# FFB_Arduino_Yoke_1_2_Micro.net
KiCad netlist of a schematic drawn in EasyEDA
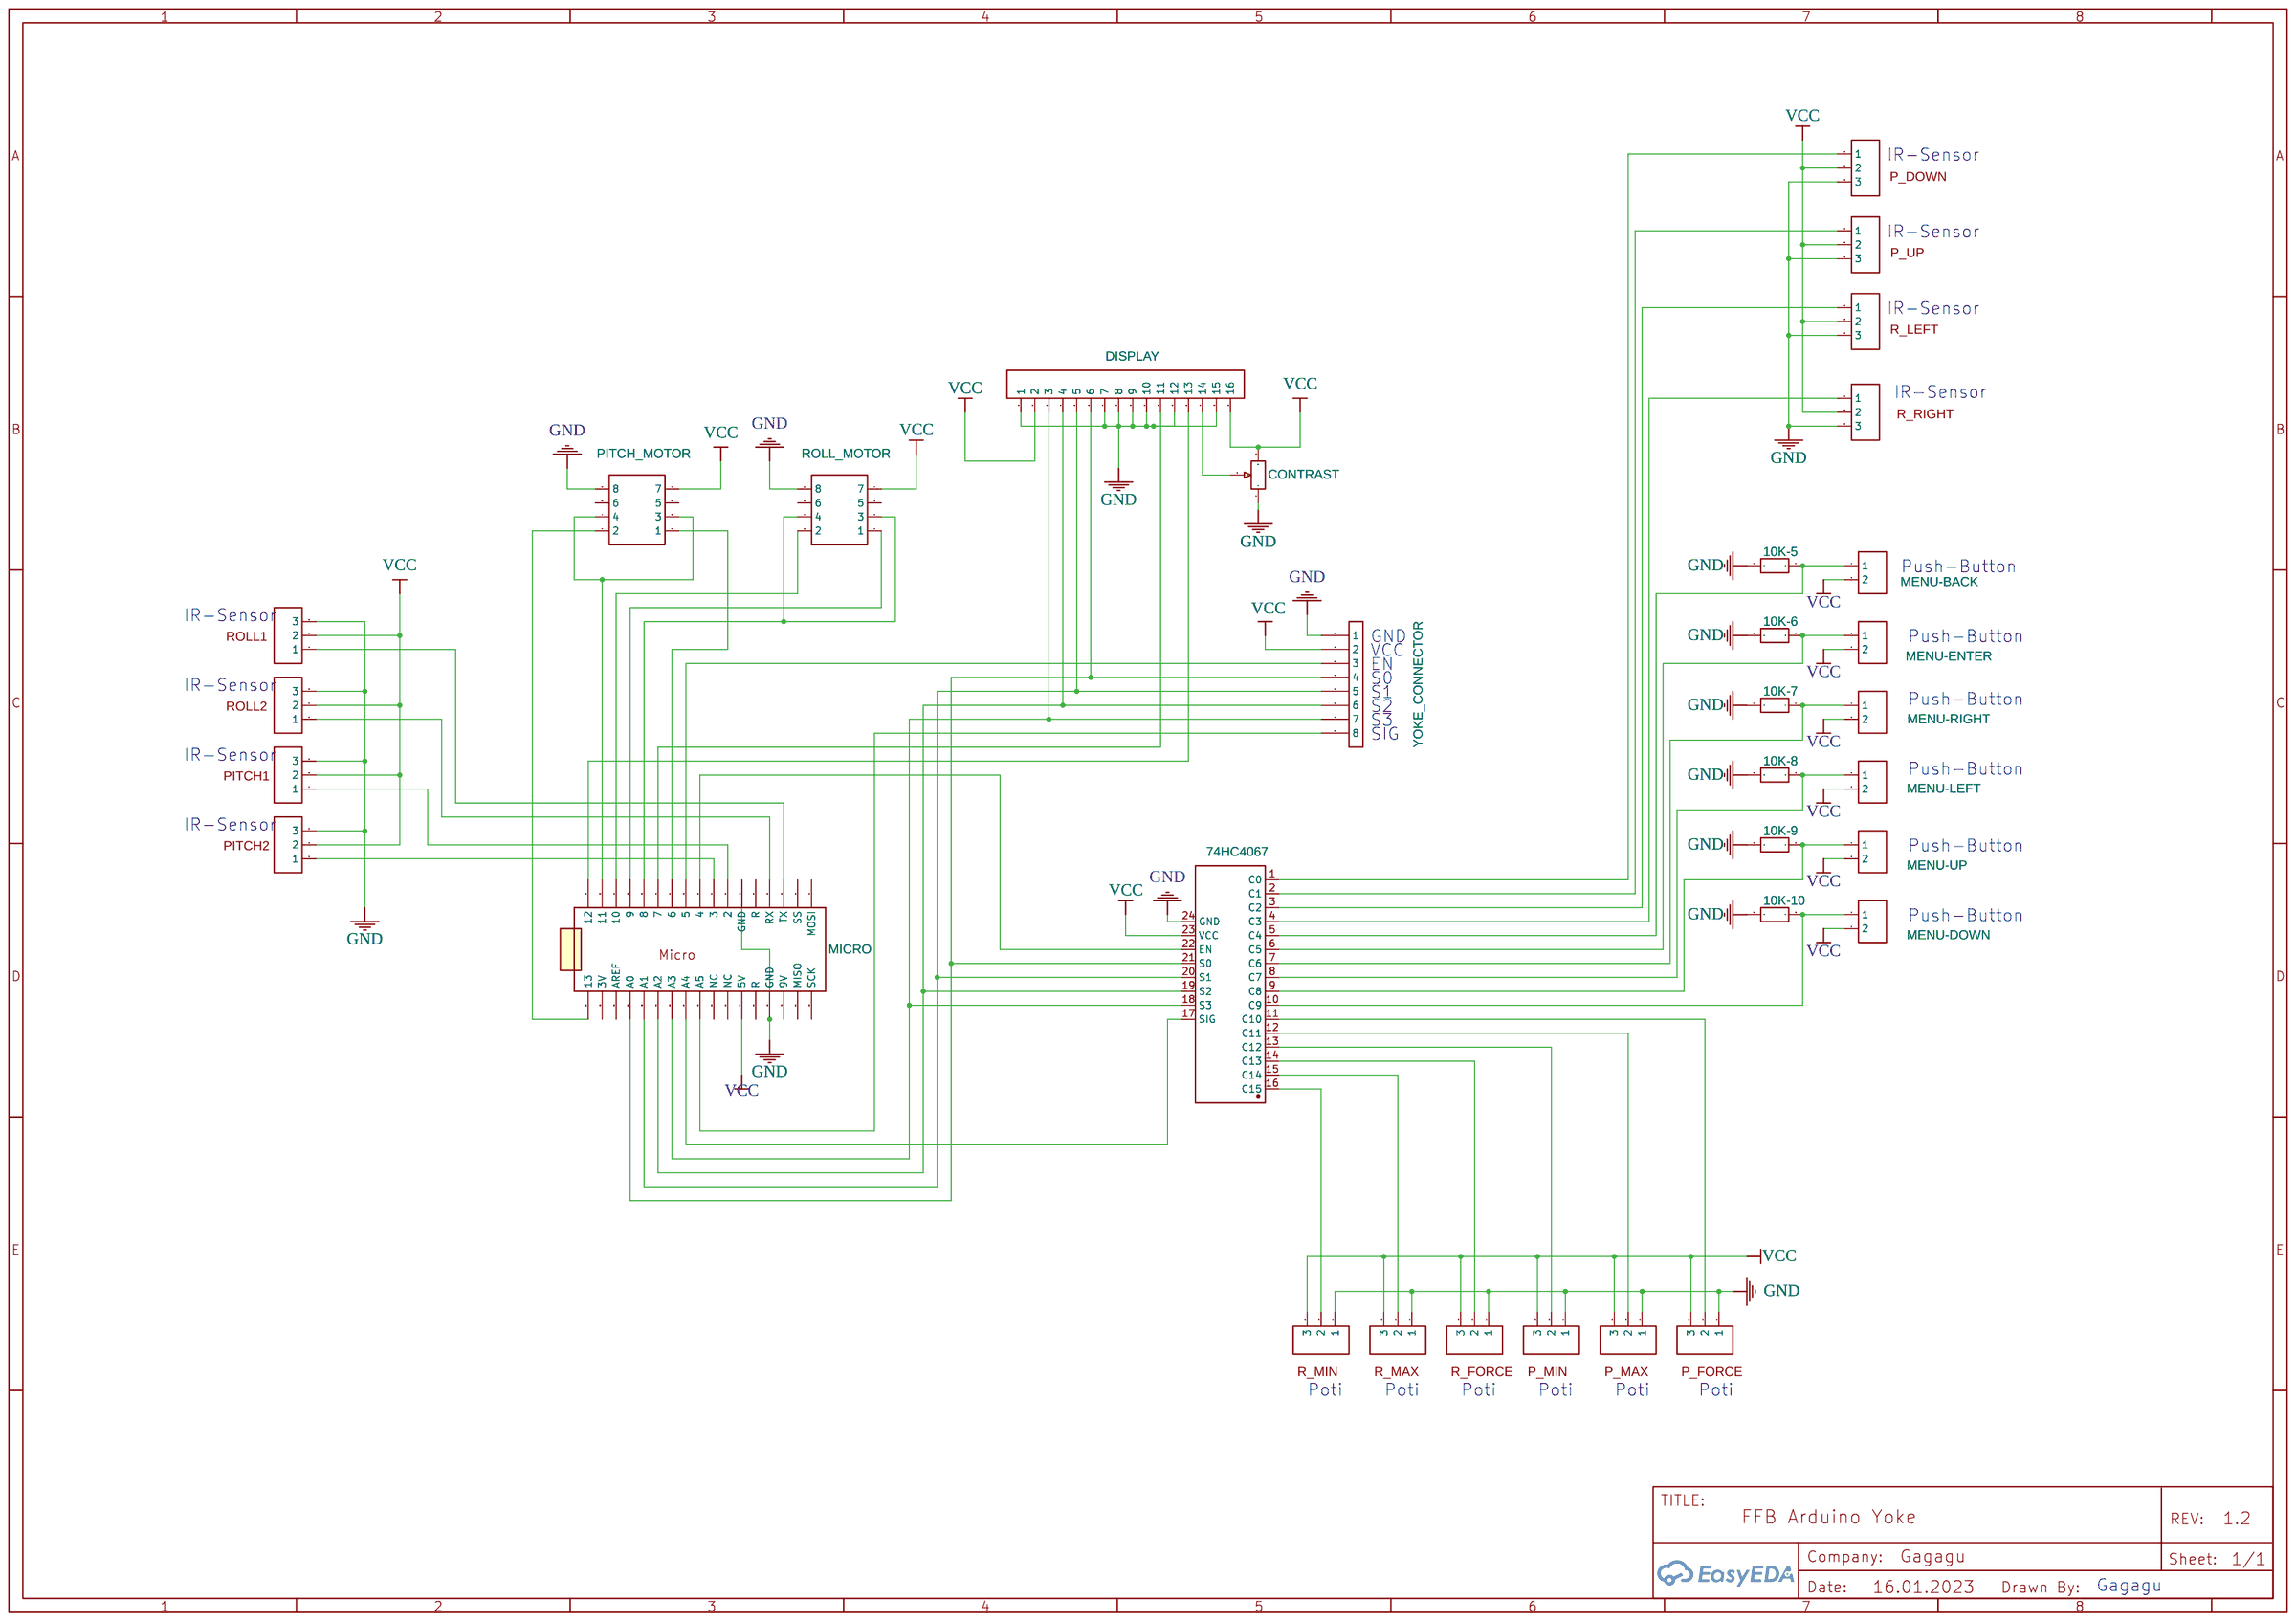
[diagram p0: schematic sheet]

(export (version "E")
  (design (tool "Eeschema 10.0.6"))
  (components
    (comp (ref "10K-5") (value "10k") (libsource (lib "") (part "R_AXIAL-0.3_EU")))
    (comp (ref "10K-6") (value "10k") (libsource (lib "") (part "R_AXIAL-0.3_EU")))
    (comp (ref "10K-7") (value "10k") (libsource (lib "") (part "R_AXIAL-0.3_EU")))
    (comp (ref "10K-8") (value "10k") (libsource (lib "") (part "R_AXIAL-0.3_EU")))
    (comp (ref "10K-9") (value "10k") (libsource (lib "") (part "R_AXIAL-0.3_EU")))
    (comp (ref "10K-10") (value "10k") (libsource (lib "") (part "R_AXIAL-0.3_EU")))
    (comp (ref "74HC4067")
      (value "MUX CD74HC4067")
      (fields (field (name "BOM_Supplier Part") "420243"))
      (libsource (lib "") (part "16-Kanal Analog/Digital Multiplexer MUX CD74HC4067"))
    )
    (comp (ref "CONTRAST") (value "R_3386P_EU") (libsource (lib "") (part "R_3386P_EU")))
    (comp (ref "DISPLAY") (value "HDR-M-2.54_1x16") (libsource (lib "") (part "HDR-M-2.54_1x16")))
    (comp (ref "MENU-BACK")
      (value "HDR-F-2.54_1x2")
      (fields (field (name "BOM_Supplier Part") "C49661"))
      (libsource (lib "") (part "HDR-F-2.54_1x2_1"))
    )
    (comp (ref "MENU-DOWN")
      (value "HDR-F-2.54_1x2")
      (fields (field (name "BOM_Supplier Part") "C49661"))
      (libsource (lib "") (part "HDR-F-2.54_1x2_4"))
    )
    (comp (ref "MENU-ENTER")
      (value "HDR-F-2.54_1x2")
      (fields (field (name "BOM_Supplier Part") "C49661"))
      (libsource (lib "") (part "HDR-F-2.54_1x2"))
    )
    (comp (ref "MENU-LEFT")
      (value "HDR-F-2.54_1x2")
      (fields (field (name "BOM_Supplier Part") "C49661"))
      (libsource (lib "") (part "HDR-F-2.54_1x2_3"))
    )
    (comp (ref "MENU-RIGHT")
      (value "HDR-F-2.54_1x2")
      (fields (field (name "BOM_Supplier Part") "C49661"))
      (libsource (lib "") (part "HDR-F-2.54_1x2_5"))
    )
    (comp (ref "MENU-UP")
      (value "HDR-F-2.54_1x2")
      (fields (field (name "BOM_Supplier Part") "C49661"))
      (libsource (lib "") (part "HDR-F-2.54_1x2_2"))
    )
    (comp (ref "MICRO") (value "ARDUINOMICRO") (libsource (lib "") (part "ARDUINOMICRO")))
    (comp (ref "PITCH1")
      (value "Multiturn POT 10K")
      (fields (field (name "BOM_Supplier Part") "C146690"))
      (libsource (lib "") (part "HDR-F-2.54_1x3_5"))
    )
    (comp (ref "PITCH2")
      (value "Multiturn POT 10K")
      (fields (field (name "BOM_Supplier Part") "C146690"))
      (libsource (lib "") (part "HDR-F-2.54_1x3_1"))
    )
    (comp (ref "PITCH_MOTOR")
      (value "HDR-F-2.54_2x4")
      (fields (field (name "BOM_Supplier Part") "C239344"))
      (libsource (lib "") (part "HDR-F-2.54_2x4"))
    )
    (comp (ref "P_DOWN")
      (value "Multiturn POT 10K")
      (fields (field (name "BOM_Supplier Part") "C146690"))
      (libsource (lib "") (part "HDR-F-2.54_1x3_9"))
    )
    (comp (ref "P_FORCE")
      (value "Multiturn POT 10K")
      (fields (field (name "BOM_Supplier Part") "C146690"))
      (libsource (lib "") (part "HDR-F-2.54_1x3_11"))
    )
    (comp (ref "P_M;IN")
      (value "Multiturn POT 10K")
      (fields (field (name "BOM_Supplier Part") "C146690"))
      (libsource (lib "") (part "HDR-F-2.54_1x3_12"))
    )
    (comp (ref "P_MAX")
      (value "Multiturn POT 10K")
      (fields (field (name "BOM_Supplier Part") "C146690"))
      (libsource (lib "") (part "HDR-F-2.54_1x3_13"))
    )
    (comp (ref "P_UP")
      (value "Multiturn POT 10K")
      (fields (field (name "BOM_Supplier Part") "C146690"))
      (libsource (lib "") (part "HDR-F-2.54_1x3_7"))
    )
    (comp (ref "ROLL1")
      (value "Multiturn POT 10K")
      (fields (field (name "BOM_Supplier Part") "C146690"))
      (libsource (lib "") (part "HDR-F-2.54_1x3_10"))
    )
    (comp (ref "ROLL2")
      (value "Multiturn POT 10K")
      (fields (field (name "BOM_Supplier Part") "C146690"))
      (libsource (lib "") (part "HDR-F-2.54_1x3"))
    )
    (comp (ref "ROLL_MOTOR")
      (value "HDR-F-2.54_2x4")
      (fields (field (name "BOM_Supplier Part") "C239344"))
      (libsource (lib "") (part "HDR-F-2.54_2x4_1"))
    )
    (comp (ref "R_FORCE")
      (value "Multiturn POT 10K")
      (fields (field (name "BOM_Supplier Part") "C146690"))
      (libsource (lib "") (part "HDR-F-2.54_1x3_6"))
    )
    (comp (ref "R_LEFT")
      (value "Multiturn POT 10K")
      (fields (field (name "BOM_Supplier Part") "C146690"))
      (libsource (lib "") (part "HDR-F-2.54_1x3_2"))
    )
    (comp (ref "R_MAX")
      (value "Multiturn POT 10K")
      (fields (field (name "BOM_Supplier Part") "C146690"))
      (libsource (lib "") (part "HDR-F-2.54_1x3_8"))
    )
    (comp (ref "R_MIN")
      (value "Multiturn POT 10K")
      (fields (field (name "BOM_Supplier Part") "C146690"))
      (libsource (lib "") (part "HDR-F-2.54_1x3_3"))
    )
    (comp (ref "R_RIGHT")
      (value "Multiturn POT 10K")
      (fields (field (name "BOM_Supplier Part") "C146690"))
      (libsource (lib "") (part "HDR-F-2.54_1x3_4"))
    )
    (comp (ref "YOKE_CONNECTOR")
      (value "Yoke Connector")
      (fields (field (name "BOM_Manufacturer Part") "Conector_dupont"))
      (libsource (lib "") (part "DUPONT_1X8"))
    )
  )
  (nets
    (net (code "1") (name "GND") (class "Default")
      (node (ref "10K-10") (pin "1") (pinfunction "1_1") (pintype "unspecified"))
      (node (ref "10K-5") (pin "1") (pinfunction "1_1") (pintype "unspecified"))
      (node (ref "10K-6") (pin "1") (pinfunction "1_1") (pintype "unspecified"))
      (node (ref "10K-7") (pin "1") (pinfunction "1_1") (pintype "unspecified"))
      (node (ref "10K-8") (pin "1") (pinfunction "1_1") (pintype "unspecified"))
      (node (ref "10K-9") (pin "1") (pinfunction "1_1") (pintype "unspecified"))
      (node (ref "74HC4067") (pin "24") (pinfunction "GND_24") (pintype "unspecified"))
      (node (ref "CONTRAST") (pin "1") (pinfunction "1_1") (pintype "input"))
      (node (ref "DISPLAY") (pin "1") (pinfunction "1_1") (pintype "unspecified"))
      (node (ref "DISPLAY") (pin "10") (pinfunction "10_10") (pintype "unspecified"))
      (node (ref "DISPLAY") (pin "12") (pinfunction "12_12") (pintype "unspecified"))
      (node (ref "DISPLAY") (pin "15") (pinfunction "15_15") (pintype "unspecified"))
      (node (ref "DISPLAY") (pin "7") (pinfunction "7_7") (pintype "unspecified"))
      (node (ref "DISPLAY") (pin "8") (pinfunction "8_8") (pintype "unspecified"))
      (node (ref "DISPLAY") (pin "9") (pinfunction "9_9") (pintype "unspecified"))
      (node (ref "MICRO") (pin "P$12") (pinfunction "GND_P$12") (pintype "unspecified"))
      (node (ref "MICRO") (pin "P$21") (pinfunction "GND_P$21") (pintype "unspecified"))
      (node (ref "PITCH1") (pin "3") (pinfunction "3_3") (pintype "unspecified"))
      (node (ref "PITCH2") (pin "3") (pinfunction "3_3") (pintype "unspecified"))
      (node (ref "PITCH_MOTOR") (pin "8") (pinfunction "8_8") (pintype "unspecified"))
      (node (ref "P_DOWN") (pin "3") (pinfunction "3_3") (pintype "unspecified"))
      (node (ref "P_FORCE") (pin "1") (pinfunction "1_1") (pintype "unspecified"))
      (node (ref "P_M;IN") (pin "1") (pinfunction "1_1") (pintype "unspecified"))
      (node (ref "P_MAX") (pin "1") (pinfunction "1_1") (pintype "unspecified"))
      (node (ref "P_UP") (pin "3") (pinfunction "3_3") (pintype "unspecified"))
      (node (ref "ROLL1") (pin "3") (pinfunction "3_3") (pintype "unspecified"))
      (node (ref "ROLL2") (pin "3") (pinfunction "3_3") (pintype "unspecified"))
      (node (ref "ROLL_MOTOR") (pin "8") (pinfunction "8_8") (pintype "unspecified"))
      (node (ref "R_FORCE") (pin "1") (pinfunction "1_1") (pintype "unspecified"))
      (node (ref "R_LEFT") (pin "3") (pinfunction "3_3") (pintype "unspecified"))
      (node (ref "R_MAX") (pin "1") (pinfunction "1_1") (pintype "unspecified"))
      (node (ref "R_MIN") (pin "1") (pinfunction "1_1") (pintype "unspecified"))
      (node (ref "R_RIGHT") (pin "3") (pinfunction "3_3") (pintype "unspecified"))
      (node (ref "YOKE_CONNECTOR") (pin "1") (pinfunction "1_1") (pintype "unspecified"))
    )
    (net (code "2") (name "Net-(74HC4067-C0)") (class "Default")
      (node (ref "74HC4067") (pin "1") (pinfunction "C0_1") (pintype "unspecified"))
      (node (ref "P_DOWN") (pin "1") (pinfunction "1_1") (pintype "unspecified"))
    )
    (net (code "3") (name "Net-(74HC4067-C1)") (class "Default")
      (node (ref "74HC4067") (pin "2") (pinfunction "C1_2") (pintype "unspecified"))
      (node (ref "P_UP") (pin "1") (pinfunction "1_1") (pintype "unspecified"))
    )
    (net (code "4") (name "Net-(74HC4067-C2)") (class "Default")
      (node (ref "74HC4067") (pin "3") (pinfunction "C2_3") (pintype "unspecified"))
      (node (ref "R_LEFT") (pin "1") (pinfunction "1_1") (pintype "unspecified"))
    )
    (net (code "5") (name "Net-(74HC4067-C3)") (class "Default")
      (node (ref "74HC4067") (pin "4") (pinfunction "C3_4") (pintype "unspecified"))
      (node (ref "R_RIGHT") (pin "1") (pinfunction "1_1") (pintype "unspecified"))
    )
    (net (code "6") (name "Net-(74HC4067-C4)") (class "Default")
      (node (ref "10K-5") (pin "2") (pinfunction "2_2") (pintype "unspecified"))
      (node (ref "74HC4067") (pin "5") (pinfunction "C4_5") (pintype "unspecified"))
      (node (ref "MENU-BACK") (pin "1") (pinfunction "1_1") (pintype "input"))
    )
    (net (code "7") (name "Net-(74HC4067-C5)") (class "Default")
      (node (ref "10K-6") (pin "2") (pinfunction "2_2") (pintype "unspecified"))
      (node (ref "74HC4067") (pin "6") (pinfunction "C5_6") (pintype "unspecified"))
      (node (ref "MENU-ENTER") (pin "1") (pinfunction "1_1") (pintype "input"))
    )
    (net (code "8") (name "Net-(74HC4067-C6)") (class "Default")
      (node (ref "10K-7") (pin "2") (pinfunction "2_2") (pintype "unspecified"))
      (node (ref "74HC4067") (pin "7") (pinfunction "C6_7") (pintype "unspecified"))
      (node (ref "MENU-RIGHT") (pin "1") (pinfunction "1_1") (pintype "input"))
    )
    (net (code "9") (name "Net-(74HC4067-C7)") (class "Default")
      (node (ref "10K-8") (pin "2") (pinfunction "2_2") (pintype "unspecified"))
      (node (ref "74HC4067") (pin "8") (pinfunction "C7_8") (pintype "unspecified"))
      (node (ref "MENU-LEFT") (pin "1") (pinfunction "1_1") (pintype "input"))
    )
    (net (code "10") (name "Net-(74HC4067-C8)") (class "Default")
      (node (ref "10K-9") (pin "2") (pinfunction "2_2") (pintype "unspecified"))
      (node (ref "74HC4067") (pin "9") (pinfunction "C8_9") (pintype "unspecified"))
      (node (ref "MENU-UP") (pin "1") (pinfunction "1_1") (pintype "input"))
    )
    (net (code "11") (name "Net-(74HC4067-C9)") (class "Default")
      (node (ref "10K-10") (pin "2") (pinfunction "2_2") (pintype "unspecified"))
      (node (ref "74HC4067") (pin "10") (pinfunction "C9_10") (pintype "unspecified"))
      (node (ref "MENU-DOWN") (pin "1") (pinfunction "1_1") (pintype "input"))
    )
    (net (code "12") (name "Net-(74HC4067-C10)") (class "Default")
      (node (ref "74HC4067") (pin "11") (pinfunction "C10_11") (pintype "unspecified"))
      (node (ref "P_FORCE") (pin "2") (pinfunction "2_2") (pintype "unspecified"))
    )
    (net (code "13") (name "Net-(74HC4067-C11)") (class "Default")
      (node (ref "74HC4067") (pin "12") (pinfunction "C11_12") (pintype "unspecified"))
      (node (ref "P_MAX") (pin "2") (pinfunction "2_2") (pintype "unspecified"))
    )
    (net (code "14") (name "Net-(74HC4067-C12)") (class "Default")
      (node (ref "74HC4067") (pin "13") (pinfunction "C12_13") (pintype "unspecified"))
      (node (ref "P_M;IN") (pin "2") (pinfunction "2_2") (pintype "unspecified"))
    )
    (net (code "15") (name "Net-(74HC4067-C13)") (class "Default")
      (node (ref "74HC4067") (pin "14") (pinfunction "C13_14") (pintype "unspecified"))
      (node (ref "R_FORCE") (pin "2") (pinfunction "2_2") (pintype "unspecified"))
    )
    (net (code "16") (name "Net-(74HC4067-C14)") (class "Default")
      (node (ref "74HC4067") (pin "15") (pinfunction "C14_15") (pintype "unspecified"))
      (node (ref "R_MAX") (pin "2") (pinfunction "2_2") (pintype "unspecified"))
    )
    (net (code "17") (name "Net-(74HC4067-C15)") (class "Default")
      (node (ref "74HC4067") (pin "16") (pinfunction "C15_16") (pintype "unspecified"))
      (node (ref "R_MIN") (pin "2") (pinfunction "2_2") (pintype "unspecified"))
    )
    (net (code "18") (name "Net-(74HC4067-EN)") (class "Default")
      (node (ref "74HC4067") (pin "22") (pinfunction "EN_22") (pintype "unspecified"))
      (node (ref "MICRO") (pin "P$9") (pinfunction "4_P$9") (pintype "unspecified"))
    )
    (net (code "19") (name "Net-(74HC4067-S0)") (class "Default")
      (node (ref "74HC4067") (pin "21") (pinfunction "S0_21") (pintype "unspecified"))
      (node (ref "DISPLAY") (pin "6") (pinfunction "6_6") (pintype "unspecified"))
      (node (ref "MICRO") (pin "P$31") (pinfunction "A0_P$31") (pintype "unspecified"))
      (node (ref "YOKE_CONNECTOR") (pin "4") (pinfunction "4_4") (pintype "unspecified"))
    )
    (net (code "20") (name "Net-(74HC4067-S1)") (class "Default")
      (node (ref "74HC4067") (pin "20") (pinfunction "S1_20") (pintype "unspecified"))
      (node (ref "DISPLAY") (pin "5") (pinfunction "5_5") (pintype "unspecified"))
      (node (ref "MICRO") (pin "P$30") (pinfunction "A1_P$30") (pintype "unspecified"))
      (node (ref "YOKE_CONNECTOR") (pin "5") (pinfunction "5_5") (pintype "unspecified"))
    )
    (net (code "21") (name "Net-(74HC4067-S2)") (class "Default")
      (node (ref "74HC4067") (pin "19") (pinfunction "S2_19") (pintype "unspecified"))
      (node (ref "DISPLAY") (pin "4") (pinfunction "4_4") (pintype "unspecified"))
      (node (ref "MICRO") (pin "P$29") (pinfunction "A2_P$29") (pintype "unspecified"))
      (node (ref "YOKE_CONNECTOR") (pin "6") (pinfunction "6_6") (pintype "unspecified"))
    )
    (net (code "22") (name "Net-(74HC4067-S3)") (class "Default")
      (node (ref "74HC4067") (pin "18") (pinfunction "S3_18") (pintype "unspecified"))
      (node (ref "DISPLAY") (pin "3") (pinfunction "3_3") (pintype "unspecified"))
      (node (ref "MICRO") (pin "P$28") (pinfunction "A3_P$28") (pintype "unspecified"))
      (node (ref "YOKE_CONNECTOR") (pin "7") (pinfunction "7_7") (pintype "unspecified"))
    )
    (net (code "23") (name "Net-(74HC4067-SIG)") (class "Default")
      (node (ref "74HC4067") (pin "17") (pinfunction "SIG_17") (pintype "unspecified"))
      (node (ref "MICRO") (pin "P$27") (pinfunction "A4_P$27") (pintype "unspecified"))
    )
    (net (code "24") (name "Net-(CONTRAST-Pad2)") (class "Default")
      (node (ref "CONTRAST") (pin "2") (pinfunction "2_2") (pintype "input"))
      (node (ref "DISPLAY") (pin "14") (pinfunction "14_14") (pintype "unspecified"))
    )
    (net (code "25") (name "Net-(MICRO-2)") (class "Default")
      (node (ref "MICRO") (pin "P$11") (pinfunction "2_P$11") (pintype "unspecified"))
      (node (ref "PITCH1") (pin "1") (pinfunction "1_1") (pintype "unspecified"))
    )
    (net (code "26") (name "Net-(MICRO-3)") (class "Default")
      (node (ref "MICRO") (pin "P$10") (pinfunction "3_P$10") (pintype "unspecified"))
      (node (ref "PITCH2") (pin "1") (pinfunction "1_1") (pintype "unspecified"))
    )
    (net (code "27") (name "Net-(MICRO-5)") (class "Default")
      (node (ref "MICRO") (pin "P$8") (pinfunction "5_P$8") (pintype "unspecified"))
      (node (ref "YOKE_CONNECTOR") (pin "3") (pinfunction "3_3") (pintype "unspecified"))
    )
    (net (code "28") (name "Net-(MICRO-6)") (class "Default")
      (node (ref "MICRO") (pin "P$7") (pinfunction "6_P$7") (pintype "unspecified"))
      (node (ref "PITCH_MOTOR") (pin "1") (pinfunction "1_1") (pintype "unspecified"))
    )
    (net (code "29") (name "Net-(MICRO-7)") (class "Default")
      (node (ref "DISPLAY") (pin "11") (pinfunction "11_11") (pintype "unspecified"))
      (node (ref "MICRO") (pin "P$6") (pinfunction "7_P$6") (pintype "unspecified"))
    )
    (net (code "30") (name "Net-(MICRO-8)") (class "Default")
      (node (ref "MICRO") (pin "P$5") (pinfunction "8_P$5") (pintype "unspecified"))
      (node (ref "ROLL_MOTOR") (pin "3") (pinfunction "3_3") (pintype "unspecified"))
      (node (ref "ROLL_MOTOR") (pin "4") (pinfunction "4_4") (pintype "unspecified"))
    )
    (net (code "31") (name "Net-(MICRO-9)") (class "Default")
      (node (ref "MICRO") (pin "P$4") (pinfunction "9_P$4") (pintype "unspecified"))
      (node (ref "ROLL_MOTOR") (pin "1") (pinfunction "1_1") (pintype "unspecified"))
    )
    (net (code "32") (name "Net-(MICRO-10)") (class "Default")
      (node (ref "MICRO") (pin "P$3") (pinfunction "10_P$3") (pintype "unspecified"))
      (node (ref "ROLL_MOTOR") (pin "2") (pinfunction "2_2") (pintype "unspecified"))
    )
    (net (code "33") (name "Net-(MICRO-11)") (class "Default")
      (node (ref "MICRO") (pin "P$2") (pinfunction "11_P$2") (pintype "unspecified"))
      (node (ref "PITCH_MOTOR") (pin "3") (pinfunction "3_3") (pintype "unspecified"))
      (node (ref "PITCH_MOTOR") (pin "4") (pinfunction "4_4") (pintype "unspecified"))
    )
    (net (code "34") (name "Net-(MICRO-12)") (class "Default")
      (node (ref "DISPLAY") (pin "13") (pinfunction "13_13") (pintype "unspecified"))
      (node (ref "MICRO") (pin "P$1") (pinfunction "12_P$1") (pintype "unspecified"))
    )
    (net (code "35") (name "Net-(MICRO-13)") (class "Default")
      (node (ref "MICRO") (pin "P$34") (pinfunction "13_P$34") (pintype "unspecified"))
      (node (ref "PITCH_MOTOR") (pin "2") (pinfunction "2_2") (pintype "unspecified"))
    )
    (net (code "36") (name "Net-(MICRO-A5)") (class "Default")
      (node (ref "MICRO") (pin "P$26") (pinfunction "A5_P$26") (pintype "unspecified"))
      (node (ref "YOKE_CONNECTOR") (pin "8") (pinfunction "8_8") (pintype "unspecified"))
    )
    (net (code "37") (name "Net-(MICRO-RX)") (class "Default")
      (node (ref "MICRO") (pin "P$14") (pinfunction "RX_P$14") (pintype "unspecified"))
      (node (ref "ROLL2") (pin "1") (pinfunction "1_1") (pintype "unspecified"))
    )
    (net (code "38") (name "Net-(MICRO-TX)") (class "Default")
      (node (ref "MICRO") (pin "P$15") (pinfunction "TX_P$15") (pintype "unspecified"))
      (node (ref "ROLL1") (pin "1") (pinfunction "1_1") (pintype "unspecified"))
    )
    (net (code "39") (name "VCC") (class "Default")
      (node (ref "74HC4067") (pin "23") (pinfunction "VCC_23") (pintype "unspecified"))
      (node (ref "CONTRAST") (pin "3") (pinfunction "3_3") (pintype "input"))
      (node (ref "DISPLAY") (pin "16") (pinfunction "16_16") (pintype "unspecified"))
      (node (ref "DISPLAY") (pin "2") (pinfunction "2_2") (pintype "unspecified"))
      (node (ref "MENU-BACK") (pin "2") (pinfunction "2_2") (pintype "input"))
      (node (ref "MENU-DOWN") (pin "2") (pinfunction "2_2") (pintype "input"))
      (node (ref "MENU-ENTER") (pin "2") (pinfunction "2_2") (pintype "input"))
      (node (ref "MENU-LEFT") (pin "2") (pinfunction "2_2") (pintype "input"))
      (node (ref "MENU-RIGHT") (pin "2") (pinfunction "2_2") (pintype "input"))
      (node (ref "MENU-UP") (pin "2") (pinfunction "2_2") (pintype "input"))
      (node (ref "MICRO") (pin "P$23") (pinfunction "5V_P$23") (pintype "unspecified"))
      (node (ref "PITCH1") (pin "2") (pinfunction "2_2") (pintype "unspecified"))
      (node (ref "PITCH2") (pin "2") (pinfunction "2_2") (pintype "unspecified"))
      (node (ref "PITCH_MOTOR") (pin "7") (pinfunction "7_7") (pintype "unspecified"))
      (node (ref "P_DOWN") (pin "2") (pinfunction "2_2") (pintype "unspecified"))
      (node (ref "P_FORCE") (pin "3") (pinfunction "3_3") (pintype "unspecified"))
      (node (ref "P_M;IN") (pin "3") (pinfunction "3_3") (pintype "unspecified"))
      (node (ref "P_MAX") (pin "3") (pinfunction "3_3") (pintype "unspecified"))
      (node (ref "P_UP") (pin "2") (pinfunction "2_2") (pintype "unspecified"))
      (node (ref "ROLL1") (pin "2") (pinfunction "2_2") (pintype "unspecified"))
      (node (ref "ROLL2") (pin "2") (pinfunction "2_2") (pintype "unspecified"))
      (node (ref "ROLL_MOTOR") (pin "7") (pinfunction "7_7") (pintype "unspecified"))
      (node (ref "R_FORCE") (pin "3") (pinfunction "3_3") (pintype "unspecified"))
      (node (ref "R_LEFT") (pin "2") (pinfunction "2_2") (pintype "unspecified"))
      (node (ref "R_MAX") (pin "3") (pinfunction "3_3") (pintype "unspecified"))
      (node (ref "R_MIN") (pin "3") (pinfunction "3_3") (pintype "unspecified"))
      (node (ref "R_RIGHT") (pin "2") (pinfunction "2_2") (pintype "unspecified"))
      (node (ref "YOKE_CONNECTOR") (pin "2") (pinfunction "2_2") (pintype "unspecified"))
    )
    (net (code "40") (name "unconnected-(MICRO-3V-PadP$33)") (class "Default")
      (node (ref "MICRO") (pin "P$33") (pinfunction "3V_P$33") (pintype "unspecified"))
    )
    (net (code "41") (name "unconnected-(MICRO-9V-PadP$20)") (class "Default")
      (node (ref "MICRO") (pin "P$20") (pinfunction "9V_P$20") (pintype "unspecified"))
    )
    (net (code "42") (name "unconnected-(MICRO-AREF-PadP$32)") (class "Default")
      (node (ref "MICRO") (pin "P$32") (pinfunction "AREF_P$32") (pintype "unspecified"))
    )
    (net (code "43") (name "unconnected-(MICRO-MISO-PadP$19)") (class "Default")
      (node (ref "MICRO") (pin "P$19") (pinfunction "MISO_P$19") (pintype "unspecified"))
    )
    (net (code "44") (name "unconnected-(MICRO-MOSI-PadP$17)") (class "Default")
      (node (ref "MICRO") (pin "P$17") (pinfunction "MOSI_P$17") (pintype "unspecified"))
    )
    (net (code "45") (name "unconnected-(MICRO-NC-PadP$24)") (class "Default")
      (node (ref "MICRO") (pin "P$24") (pinfunction "NC_P$24") (pintype "unspecified"))
    )
    (net (code "46") (name "unconnected-(MICRO-NC-PadP$25)") (class "Default")
      (node (ref "MICRO") (pin "P$25") (pinfunction "NC_P$25") (pintype "unspecified"))
    )
    (net (code "47") (name "unconnected-(MICRO-R-PadP$13)") (class "Default")
      (node (ref "MICRO") (pin "P$13") (pinfunction "R_P$13") (pintype "unspecified"))
    )
    (net (code "48") (name "unconnected-(MICRO-R-PadP$22)") (class "Default")
      (node (ref "MICRO") (pin "P$22") (pinfunction "R_P$22") (pintype "unspecified"))
    )
    (net (code "49") (name "unconnected-(MICRO-SCK-PadP$18)") (class "Default")
      (node (ref "MICRO") (pin "P$18") (pinfunction "SCK_P$18") (pintype "unspecified"))
    )
    (net (code "50") (name "unconnected-(MICRO-SS-PadP$16)") (class "Default")
      (node (ref "MICRO") (pin "P$16") (pinfunction "SS_P$16") (pintype "unspecified"))
    )
    (net (code "51") (name "unconnected-(PITCH_MOTOR-Pad5)") (class "Default")
      (node (ref "PITCH_MOTOR") (pin "5") (pinfunction "5_5") (pintype "unspecified"))
    )
    (net (code "52") (name "unconnected-(PITCH_MOTOR-Pad6)") (class "Default")
      (node (ref "PITCH_MOTOR") (pin "6") (pinfunction "6_6") (pintype "unspecified"))
    )
    (net (code "53") (name "unconnected-(ROLL_MOTOR-Pad5)") (class "Default")
      (node (ref "ROLL_MOTOR") (pin "5") (pinfunction "5_5") (pintype "unspecified"))
    )
    (net (code "54") (name "unconnected-(ROLL_MOTOR-Pad6)") (class "Default")
      (node (ref "ROLL_MOTOR") (pin "6") (pinfunction "6_6") (pintype "unspecified"))
    )
  )
)
